# ABC2.net
KiCad netlist of a schematic drawn in Altium Designer
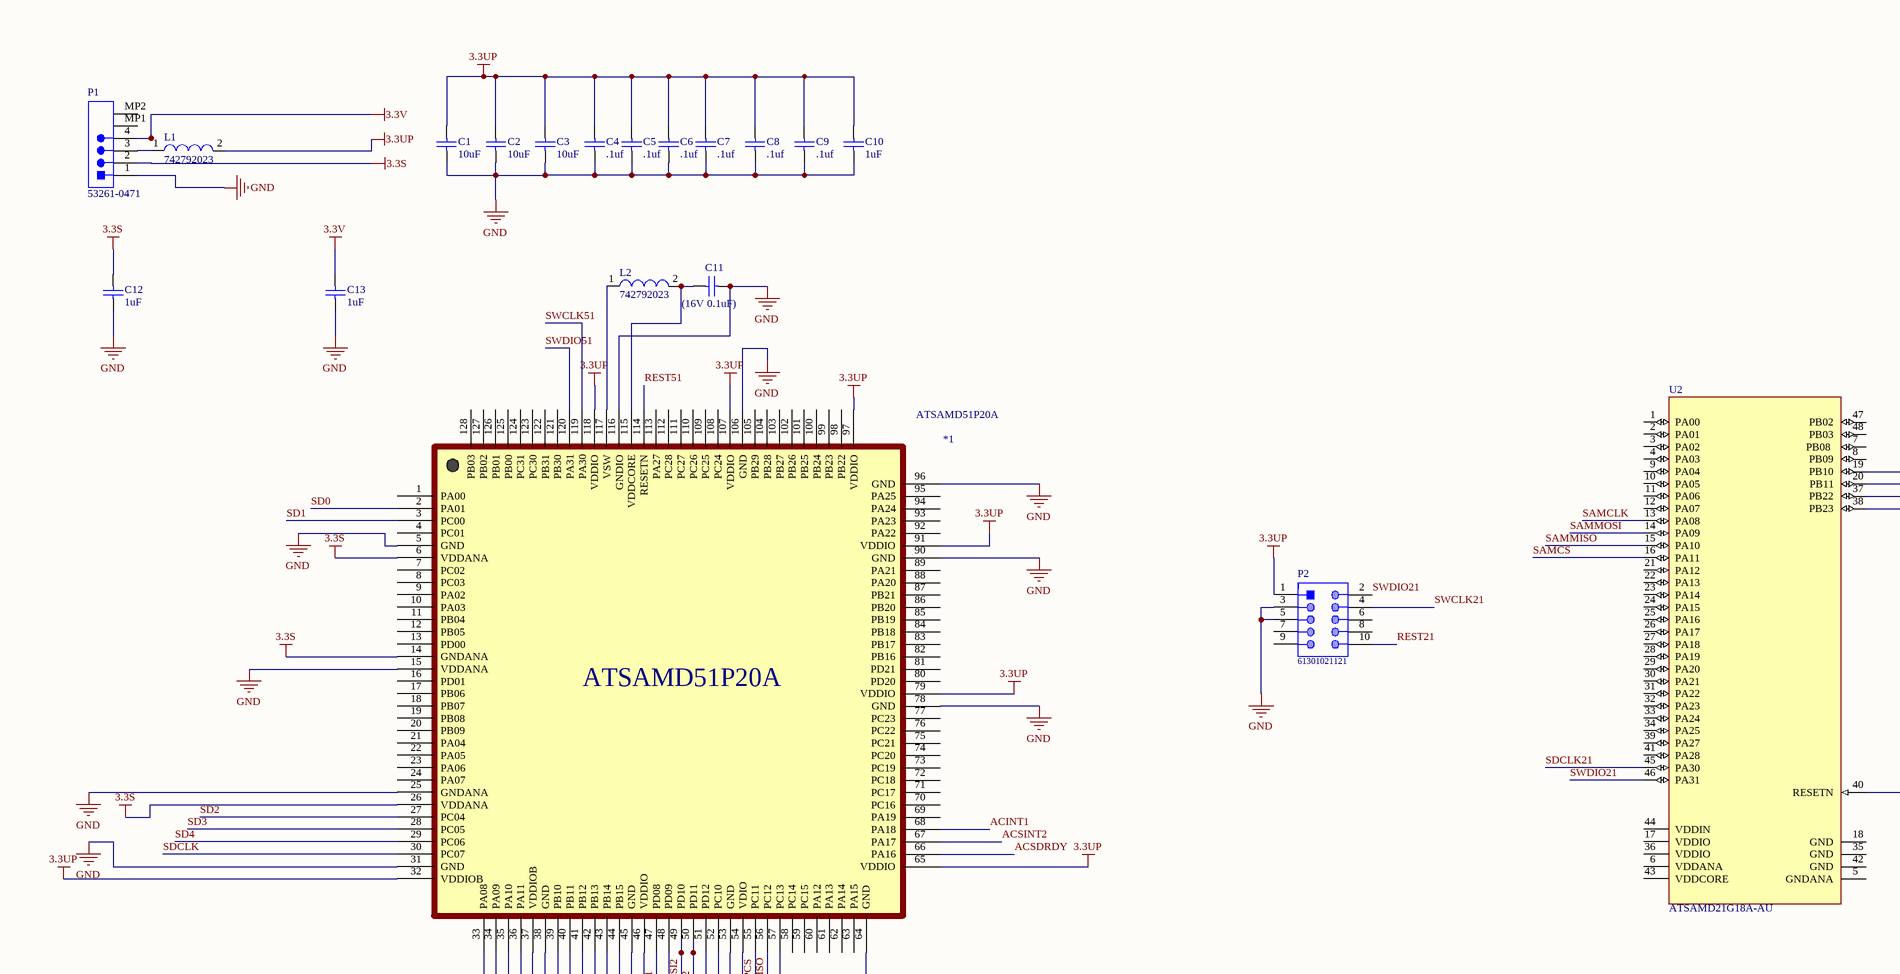
[diagram p0: ABC2.SchDoc, top left]
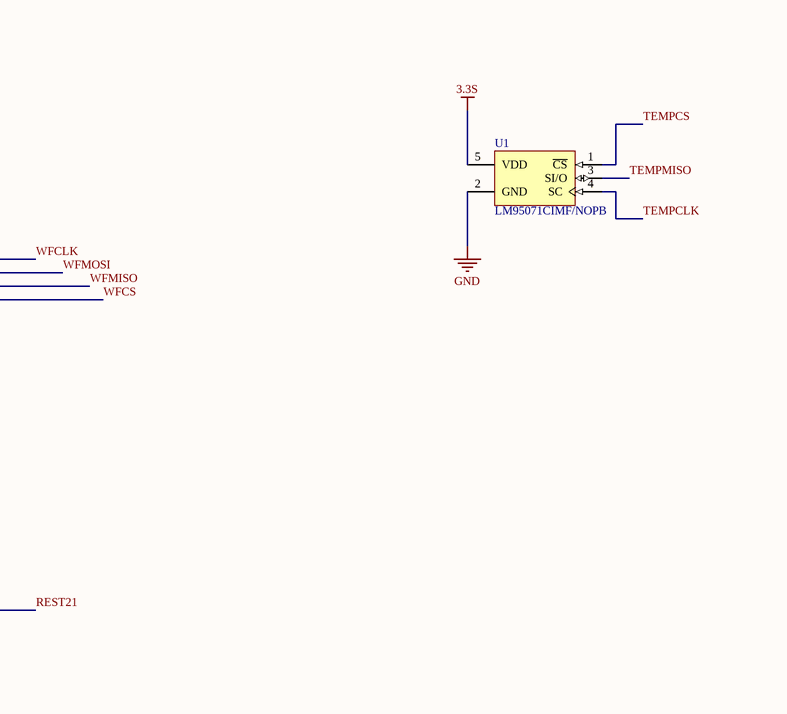
[diagram p1: ABC2.SchDoc, top right]
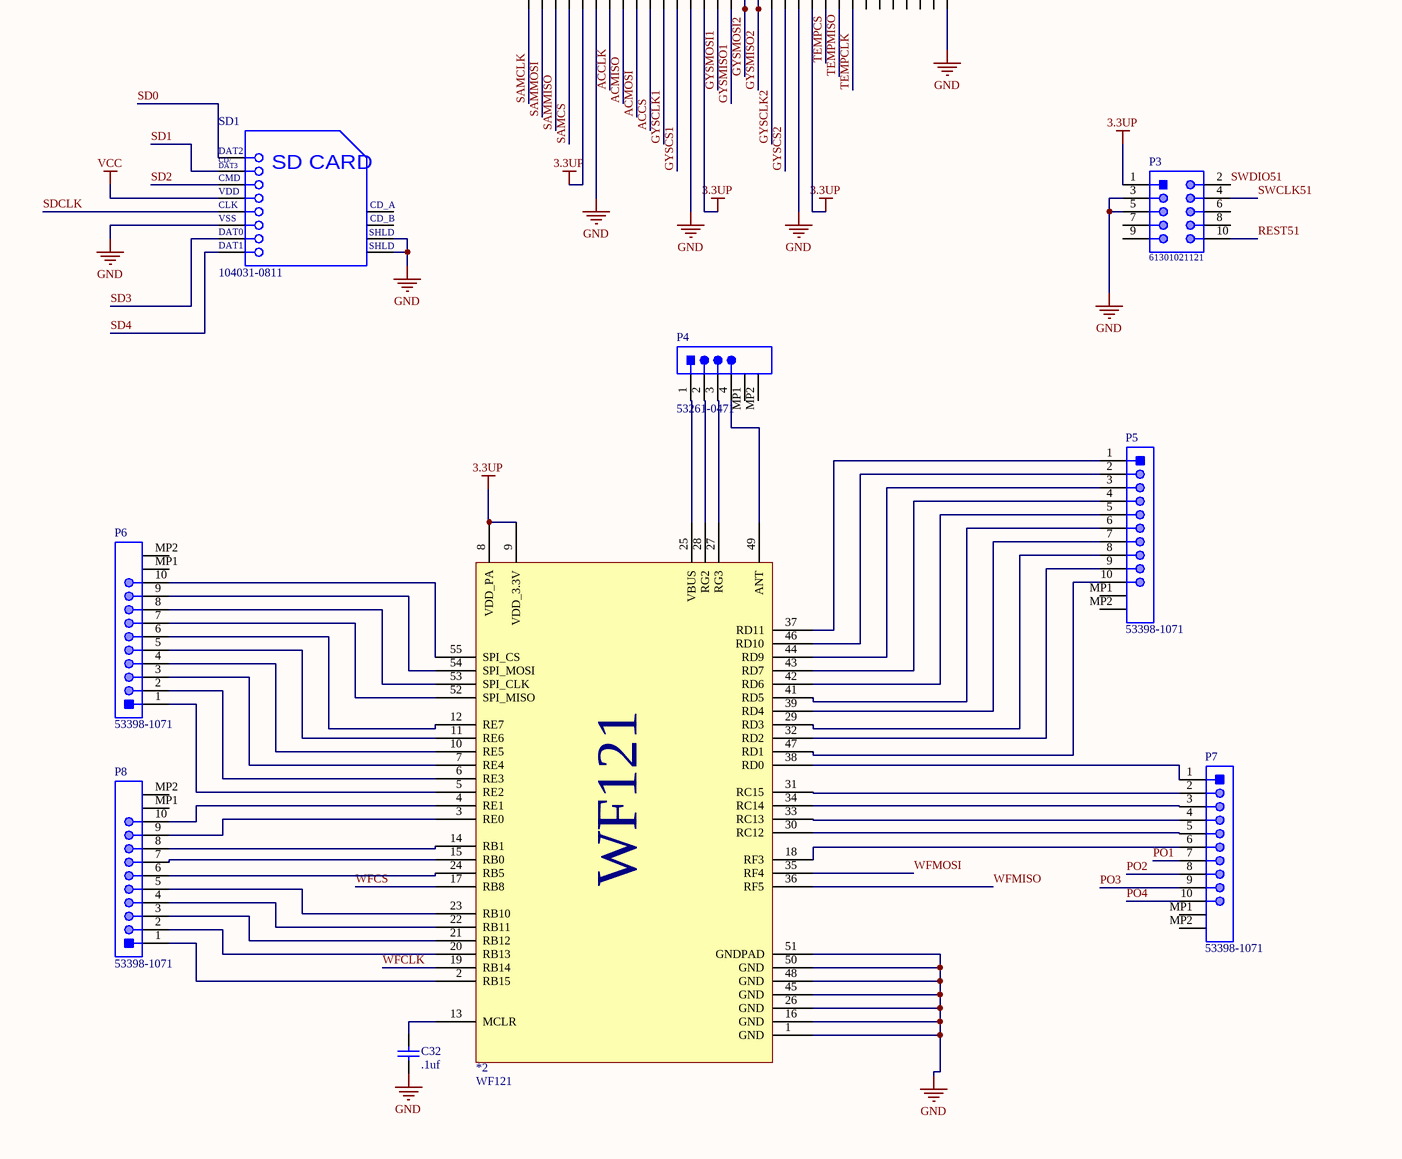
[diagram p2: ABC2.SchDoc, bottom left]
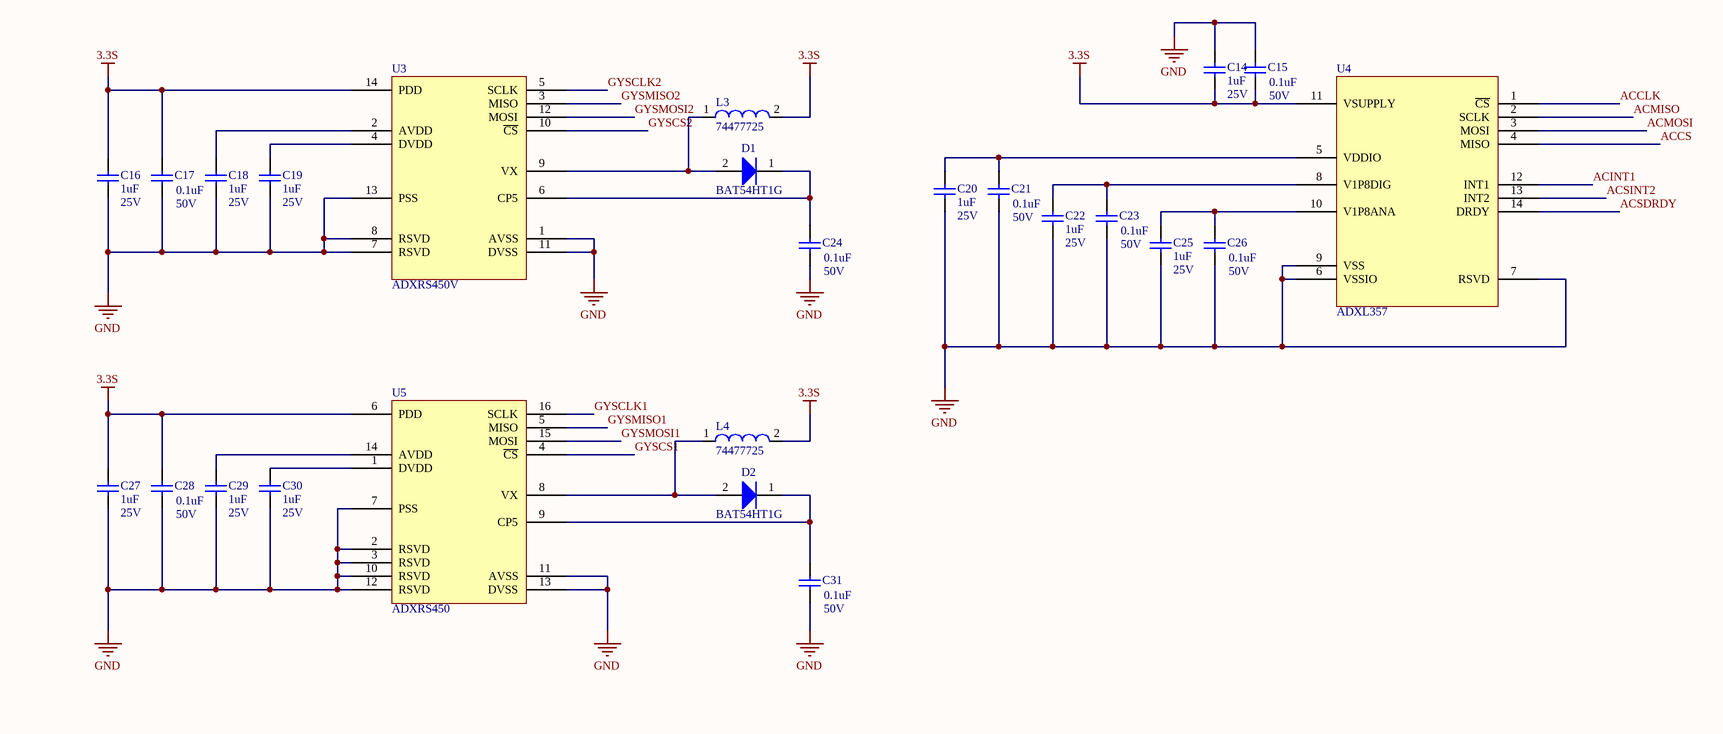
[diagram p3: ABC2.SchDoc, bottom right]

(export (version "E")
  (design (tool "Eeschema 10.0.6"))
  (components
    (comp (ref "*1")
      (value "ATSAMD51P20A")
      (footprint "ATSAMD51P20A")
      (description "https://www.microchip.com/wwwproducts/en/ATSAMD51P20A#additional-features")
      (libsource (lib "ATSAMD51P20A") (part "ATSAMD51P20A"))
    )
    (comp (ref "*2")
      (value "WF121")
      (footprint "WF121:WF121")
      (description "WF121 WIFI Module.")
      (libsource (lib "WF121") (part "WF121"))
    )
    (comp (ref "C1")
      (value "10uF")
      (footprint "CAPC1608X90X35NL10T15")
      (fields (field (name "PART NUMBER") "GRM188R60J106ME47D") (field (name "MANUFACTURER") "Murata"))
      (libsource (lib "Altium Content Vault") (part "CAP"))
    )
    (comp (ref "C2")
      (value "10uF")
      (footprint "CAPC1608X90X35NL10T15")
      (fields (field (name "PART NUMBER") "GRM188R60J106ME47D") (field (name "MANUFACTURER") "Murata"))
      (libsource (lib "Altium Content Vault") (part "CAP"))
    )
    (comp (ref "C3")
      (value "10uF")
      (footprint "CAPC1608X90X35NL10T15")
      (fields (field (name "PART NUMBER") "GRM188R60J106ME47D") (field (name "MANUFACTURER") "Murata"))
      (libsource (lib "Altium Content Vault") (part "CAP"))
    )
    (comp (ref "C4")
      (value ".1uf")
      (footprint "CAPC2013X94X50NL20T25")
      (fields
        (field (name "PART NUMBER") "0805YC104KAT2A")
        (field (name "MANUFACTURER") "AVX Interconnect / Elco")
      )
      (libsource (lib "Altium Content Vault") (part "CAP"))
    )
    (comp (ref "C5")
      (value ".1uf")
      (footprint "CAPC2013X94X50NL20T25")
      (fields
        (field (name "PART NUMBER") "0805YC104KAT2A")
        (field (name "MANUFACTURER") "AVX Interconnect / Elco")
      )
      (libsource (lib "Altium Content Vault") (part "CAP"))
    )
    (comp (ref "C6")
      (value ".1uf")
      (footprint "CAPC2013X94X50NL20T25")
      (fields
        (field (name "PART NUMBER") "0805YC104KAT2A")
        (field (name "MANUFACTURER") "AVX Interconnect / Elco")
      )
      (libsource (lib "Altium Content Vault") (part "CAP"))
    )
    (comp (ref "C7")
      (value ".1uf")
      (footprint "CAPC2013X94X50NL20T25")
      (fields
        (field (name "PART NUMBER") "0805YC104KAT2A")
        (field (name "MANUFACTURER") "AVX Interconnect / Elco")
      )
      (libsource (lib "Altium Content Vault") (part "CAP"))
    )
    (comp (ref "C8")
      (value ".1uf")
      (footprint "CAPC2013X94X50NL20T25")
      (fields
        (field (name "PART NUMBER") "0805YC104KAT2A")
        (field (name "MANUFACTURER") "AVX Interconnect / Elco")
      )
      (libsource (lib "Altium Content Vault") (part "CAP"))
    )
    (comp (ref "C9")
      (value ".1uf")
      (footprint "CAPC2013X94X50NL20T25")
      (fields
        (field (name "PART NUMBER") "0805YC104KAT2A")
        (field (name "MANUFACTURER") "AVX Interconnect / Elco")
      )
      (libsource (lib "Altium Content Vault") (part "CAP"))
    )
    (comp (ref "C10")
      (value "1uF")
      (footprint "CAPC1608X90X35LL15T15")
      (fields
        (field (name "PART NUMBER") "0603ZC105KAT2A")
        (field (name "MANUFACTURER") "AVX Interconnect / Elco")
      )
      (libsource (lib "Altium Content Vault") (part "CAP"))
    )
    (comp (ref "C11")
      (value "(16V 0.1uF)")
      (footprint "CAPC1608X90X35LL15T15")
      (fields
        (field (name "PART NUMBER") "0603YC104MAT4A")
        (field (name "MANUFACTURER") "AVX Interconnect / Elco")
      )
      (libsource (lib "Altium Content Vault") (part "CAP"))
    )
    (comp (ref "C12")
      (value "1uF")
      (footprint "CAPC1608X90X35LL15T15")
      (fields
        (field (name "PART NUMBER") "0603ZC105KAT2A")
        (field (name "MANUFACTURER") "AVX Interconnect / Elco")
      )
      (libsource (lib "Altium Content Vault") (part "CAP"))
    )
    (comp (ref "C13")
      (value "1uF")
      (footprint "CAPC1608X90X35LL15T15")
      (fields
        (field (name "PART NUMBER") "0603ZC105KAT2A")
        (field (name "MANUFACTURER") "AVX Interconnect / Elco")
      )
      (libsource (lib "Altium Content Vault") (part "CAP"))
    )
    (comp (ref "C14")
      (value "C0805C105K3RACTU")
      (footprint "CAPC2013X140X50LL20T25")
      (fields
        (field (name "MANUFACTURER") "Kemet")
        (field (name "CAPACITANCE") "1uF")
        (field (name "VOLTAGE RATING") "25V")
      )
      (libsource (lib "Altium Content Vault") (part "CAP"))
    )
    (comp (ref "C15")
      (value "CC0805KRX7R9BB104")
      (footprint "CAPC2013X95X50ML10T25")
      (description "Chip Capacitor, 100 nF, +/- 10%, 50 V, -55 to 125 degC, 0805 (2012 Metric), RoHS, Tape and Reel")
      (fields
        (field (name "VOLTAGE RATING") "50V")
        (field (name "TOLERANCE") "10%")
        (field (name "VOLTAGE") "50V")
        (field (name "CAPACITANCE") "0.1uF")
      )
      (libsource (lib "Altium Content Vault") (part "CAP-NP-2"))
    )
    (comp (ref "C16")
      (value "C0805C105K3RACTU")
      (footprint "CAPC2013X140X50LL20T25")
      (fields
        (field (name "MANUFACTURER") "Kemet")
        (field (name "CAPACITANCE") "1uF")
        (field (name "VOLTAGE RATING") "25V")
      )
      (libsource (lib "Altium Content Vault") (part "CAP"))
    )
    (comp (ref "C17")
      (value "CC0805KRX7R9BB104")
      (footprint "CAPC2013X95X50ML10T25")
      (description "Chip Capacitor, 100 nF, +/- 10%, 50 V, -55 to 125 degC, 0805 (2012 Metric), RoHS, Tape and Reel")
      (fields
        (field (name "VOLTAGE RATING") "50V")
        (field (name "TOLERANCE") "10%")
        (field (name "VOLTAGE") "50V")
        (field (name "CAPACITANCE") "0.1uF")
      )
      (libsource (lib "Altium Content Vault") (part "CAP-NP-2"))
    )
    (comp (ref "C18")
      (value "C0805C105K3RACTU")
      (footprint "CAPC2013X140X50LL20T25")
      (fields
        (field (name "MANUFACTURER") "Kemet")
        (field (name "CAPACITANCE") "1uF")
        (field (name "VOLTAGE RATING") "25V")
      )
      (libsource (lib "Altium Content Vault") (part "CAP"))
    )
    (comp (ref "C19")
      (value "C0805C105K3RACTU")
      (footprint "CAPC2013X140X50LL20T25")
      (fields
        (field (name "MANUFACTURER") "Kemet")
        (field (name "CAPACITANCE") "1uF")
        (field (name "VOLTAGE RATING") "25V")
      )
      (libsource (lib "Altium Content Vault") (part "CAP"))
    )
    (comp (ref "C20")
      (value "C0805C105K3RACTU")
      (footprint "CAPC2013X140X50LL20T25")
      (fields
        (field (name "MANUFACTURER") "Kemet")
        (field (name "CAPACITANCE") "1uF")
        (field (name "VOLTAGE RATING") "25V")
      )
      (libsource (lib "Altium Content Vault") (part "CAP"))
    )
    (comp (ref "C21")
      (value "CC0805KRX7R9BB104")
      (footprint "CAPC2013X95X50ML10T25")
      (description "Chip Capacitor, 100 nF, +/- 10%, 50 V, -55 to 125 degC, 0805 (2012 Metric), RoHS, Tape and Reel")
      (fields
        (field (name "VOLTAGE RATING") "50V")
        (field (name "TOLERANCE") "10%")
        (field (name "VOLTAGE") "50V")
        (field (name "CAPACITANCE") "0.1uF")
      )
      (libsource (lib "Altium Content Vault") (part "CAP-NP-2"))
    )
    (comp (ref "C22")
      (value "C0805C105K3RACTU")
      (footprint "CAPC2013X140X50LL20T25")
      (fields
        (field (name "MANUFACTURER") "Kemet")
        (field (name "CAPACITANCE") "1uF")
        (field (name "VOLTAGE RATING") "25V")
      )
      (libsource (lib "Altium Content Vault") (part "CAP"))
    )
    (comp (ref "C23")
      (value "CC0805KRX7R9BB104")
      (footprint "CAPC2013X95X50ML10T25")
      (description "Chip Capacitor, 100 nF, +/- 10%, 50 V, -55 to 125 degC, 0805 (2012 Metric), RoHS, Tape and Reel")
      (fields
        (field (name "VOLTAGE RATING") "50V")
        (field (name "TOLERANCE") "10%")
        (field (name "VOLTAGE") "50V")
        (field (name "CAPACITANCE") "0.1uF")
      )
      (libsource (lib "Altium Content Vault") (part "CAP-NP-2"))
    )
    (comp (ref "C24")
      (value "CC0805KRX7R9BB104")
      (footprint "CAPC2013X95X50ML10T25")
      (description "Chip Capacitor, 100 nF, +/- 10%, 50 V, -55 to 125 degC, 0805 (2012 Metric), RoHS, Tape and Reel")
      (fields
        (field (name "VOLTAGE RATING") "50V")
        (field (name "TOLERANCE") "10%")
        (field (name "VOLTAGE") "50V")
        (field (name "CAPACITANCE") "0.1uF")
      )
      (libsource (lib "Altium Content Vault") (part "CAP-NP-2"))
    )
    (comp (ref "C25")
      (value "C0805C105K3RACTU")
      (footprint "CAPC2013X140X50LL20T25")
      (fields
        (field (name "MANUFACTURER") "Kemet")
        (field (name "CAPACITANCE") "1uF")
        (field (name "VOLTAGE RATING") "25V")
      )
      (libsource (lib "Altium Content Vault") (part "CAP"))
    )
    (comp (ref "C26")
      (value "CC0805KRX7R9BB104")
      (footprint "CAPC2013X95X50ML10T25")
      (description "Chip Capacitor, 100 nF, +/- 10%, 50 V, -55 to 125 degC, 0805 (2012 Metric), RoHS, Tape and Reel")
      (fields
        (field (name "VOLTAGE RATING") "50V")
        (field (name "TOLERANCE") "10%")
        (field (name "VOLTAGE") "50V")
        (field (name "CAPACITANCE") "0.1uF")
      )
      (libsource (lib "Altium Content Vault") (part "CAP-NP-2"))
    )
    (comp (ref "C27")
      (value "C0805C105K3RACTU")
      (footprint "CAPC2013X140X50LL20T25")
      (fields
        (field (name "MANUFACTURER") "Kemet")
        (field (name "CAPACITANCE") "1uF")
        (field (name "VOLTAGE RATING") "25V")
      )
      (libsource (lib "Altium Content Vault") (part "CAP"))
    )
    (comp (ref "C28")
      (value "CC0805KRX7R9BB104")
      (footprint "CAPC2013X95X50ML10T25")
      (description "Chip Capacitor, 100 nF, +/- 10%, 50 V, -55 to 125 degC, 0805 (2012 Metric), RoHS, Tape and Reel")
      (fields
        (field (name "VOLTAGE RATING") "50V")
        (field (name "TOLERANCE") "10%")
        (field (name "VOLTAGE") "50V")
        (field (name "CAPACITANCE") "0.1uF")
      )
      (libsource (lib "Altium Content Vault") (part "CAP-NP-2"))
    )
    (comp (ref "C29")
      (value "C0805C105K3RACTU")
      (footprint "CAPC2013X140X50LL20T25")
      (fields
        (field (name "MANUFACTURER") "Kemet")
        (field (name "CAPACITANCE") "1uF")
        (field (name "VOLTAGE RATING") "25V")
      )
      (libsource (lib "Altium Content Vault") (part "CAP"))
    )
    (comp (ref "C30")
      (value "C0805C105K3RACTU")
      (footprint "CAPC2013X140X50LL20T25")
      (fields
        (field (name "MANUFACTURER") "Kemet")
        (field (name "CAPACITANCE") "1uF")
        (field (name "VOLTAGE RATING") "25V")
      )
      (libsource (lib "Altium Content Vault") (part "CAP"))
    )
    (comp (ref "C31")
      (value "CC0805KRX7R9BB104")
      (footprint "CAPC2013X95X50ML10T25")
      (description "Chip Capacitor, 100 nF, +/- 10%, 50 V, -55 to 125 degC, 0805 (2012 Metric), RoHS, Tape and Reel")
      (fields
        (field (name "VOLTAGE RATING") "50V")
        (field (name "TOLERANCE") "10%")
        (field (name "VOLTAGE") "50V")
        (field (name "CAPACITANCE") "0.1uF")
      )
      (libsource (lib "Altium Content Vault") (part "CAP-NP-2"))
    )
    (comp (ref "C32")
      (value ".1uf")
      (footprint "CAPC2013X94X50NL20T25")
      (fields
        (field (name "PART NUMBER") "0805YC104KAT2A")
        (field (name "MANUFACTURER") "AVX Interconnect / Elco")
      )
      (libsource (lib "Altium Content Vault") (part "CAP"))
    )
    (comp (ref "D1")
      (value "BAT54HT1G")
      (footprint "ONSC-SOD-323-2-477-02_V")
      (description "Schottky Barrier Diode, 2-Pin SOD-323, Pb-Free, Tape and Reel")
      (fields (field (name "MANUFACTURER") "On Semiconductor"))
      (libsource (lib "Altium Content Vault") (part "ONSC-D-K1A2-2"))
    )
    (comp (ref "D2")
      (value "BAT54HT1G")
      (footprint "ONSC-SOD-323-2-477-02_V")
      (description "Schottky Barrier Diode, 2-Pin SOD-323, Pb-Free, Tape and Reel")
      (fields (field (name "MANUFACTURER") "On Semiconductor"))
      (libsource (lib "Altium Content Vault") (part "ONSC-D-K1A2-2"))
    )
    (comp (ref "L1")
      (value "742792023")
      (footprint "SMD-0805")
      (description "SMD EMI Suppression Ferrite Bead WE-CBF, Z = 120 Ohm")
      (libsource (lib "Altium Content Vault") (part "PAS-IND-INDUCTOR-2"))
    )
    (comp (ref "L2")
      (value "742792023")
      (footprint "SMD-0805")
      (description "SMD EMI Suppression Ferrite Bead WE-CBF, Z = 120 Ohm")
      (libsource (lib "Altium Content Vault") (part "PAS-IND-INDUCTOR-2"))
    )
    (comp (ref "L3")
      (value "74477725")
      (footprint "WE-PD-M")
      (description "SMD-Shielded Power Inductor WE-PD, L = 560 µH")
      (libsource (lib "Altium Content Vault") (part "PAS-IND-INDUCTOR-2"))
    )
    (comp (ref "L4")
      (value "74477725")
      (footprint "WE-PD-M")
      (description "SMD-Shielded Power Inductor WE-PD, L = 560 µH")
      (libsource (lib "Altium Content Vault") (part "PAS-IND-INDUCTOR-2"))
    )
    (comp (ref "P1")
      (value "53261-0471")
      (footprint "MOLEX-53261-0471_V")
      (description "Male Header, Pitch 1.25 mm, 1 x 4 Position, Height 3.4 mm, -40 to 85 degC, RoHS, Tape and Reel")
      (fields (field (name "MANUFACTURER") "Molex"))
      (libsource (lib "") (part "CN-1P-2M-R4_A_1"))
    )
    (comp (ref "P2")
      (value "61301021121")
      (footprint "61301021121")
      (description "THT Vertical Pin Header WR-PHD, Pitch 2.54 mm, Dual Row, 10 pins")
      (fields (field (name "MANUFACTURER") "Wurth Elektronik") (field (name "PUBLISHER") "WurthElektronik"))
      (libsource (lib "Altium Content Vault") (part "WE-CN-2P-M-R10"))
    )
    (comp (ref "P3")
      (value "61301021121")
      (footprint "61301021121")
      (description "THT Vertical Pin Header WR-PHD, Pitch 2.54 mm, Dual Row, 10 pins")
      (fields (field (name "MANUFACTURER") "Wurth Elektronik") (field (name "PUBLISHER") "WurthElektronik"))
      (libsource (lib "Altium Content Vault") (part "WE-CN-2P-M-R10"))
    )
    (comp (ref "P4")
      (value "53261-0471")
      (footprint "MOLEX-53261-0471_V")
      (description "Male Header, Pitch 1.25 mm, 1 x 4 Position, Height 3.4 mm, -40 to 85 degC, RoHS, Tape and Reel")
      (fields (field (name "MANUFACTURER") "Molex"))
      (libsource (lib "Altium Content Vault") (part "CN-1P-2M-R4_A"))
    )
    (comp (ref "P5")
      (value "53398-1071")
      (footprint "MOLX-53398-1071_V")
      (description "Male Header, Pitch 1.25 mm, 1 x 10 Position, Height 4.7 mm, -40 to 85 degC, RoHS, Tape and Reel")
      (fields (field (name "MANUFACTURER") "Molex"))
      (libsource (lib "") (part "CN-1P-2M-R10_1"))
    )
    (comp (ref "P6")
      (value "53398-1071")
      (footprint "MOLX-53398-1071_V")
      (description "Male Header, Pitch 1.25 mm, 1 x 10 Position, Height 4.7 mm, -40 to 85 degC, RoHS, Tape and Reel")
      (fields (field (name "MANUFACTURER") "Molex"))
      (libsource (lib "Altium Content Vault") (part "CN-1P-2M-R10"))
    )
    (comp (ref "P7")
      (value "53398-1071")
      (footprint "MOLX-53398-1071_V")
      (description "Male Header, Pitch 1.25 mm, 1 x 10 Position, Height 4.7 mm, -40 to 85 degC, RoHS, Tape and Reel")
      (fields (field (name "MANUFACTURER") "Molex"))
      (libsource (lib "") (part "CN-1P-2M-R10_1"))
    )
    (comp (ref "P8")
      (value "53398-1071")
      (footprint "MOLX-53398-1071_V")
      (description "Male Header, Pitch 1.25 mm, 1 x 10 Position, Height 4.7 mm, -40 to 85 degC, RoHS, Tape and Reel")
      (fields (field (name "MANUFACTURER") "Molex"))
      (libsource (lib "Altium Content Vault") (part "CN-1P-2M-R10"))
    )
    (comp (ref "SD1")
      (value "104031-0811")
      (footprint "MOLX-104031-0811_V")
      (description "Micro SD Card, RA, -25 to 85 degC, 8-Pin SMD, RoHS, Tape and Reel")
      (fields (field (name "MANUFACTURER") "Molex"))
      (libsource (lib "Altium Content Vault") (part "CN-SD-8-2SW-2S"))
    )
    (comp (ref "U1")
      (value "LM95071CIMF/NOPB")
      (footprint "DBV0005A_L")
      (description "SPI/MICROWIRE 13-Bit Plus Sign Temperature Sensor, 5-pin SOT-23, Pb-Free")
      (fields (field (name "MANUFACTURER") "Texas Instruments"))
      (libsource (lib "Altium Content Vault") (part "SEN-TEMP-LM95071CIMF-5"))
    )
    (comp (ref "U2")
      (value "ATSAMD21G18A-AU")
      (footprint "ATML-TQFP48_M")
      (fields (field (name "MANUFACTURER") "Atmel"))
      (libsource (lib "SAMD21") (part "CMP-2100-03585-1"))
    )
    (comp (ref "U3")
      (value "ADXRS450V")
      (footprint "LCC127P900X400X915-14N")
      (libsource (lib "CFClib") (part "ADXRS450V"))
    )
    (comp (ref "U4")
      (value "ADXL357")
      (footprint "LCCS127P605X560X220-14N")
      (libsource (lib "CFClib") (part "ADXL357"))
    )
    (comp (ref "U5")
      (value "ADXRS450")
      (footprint "SOIC127P1040X373-16N")
      (libsource (lib "CFClib") (part "ADXRS450"))
    )
  )
  (nets
    (net (code "1") (name "/ACCLK") (class "Default")
      (node (ref "*1") (pin "39") (pinfunction "PB10_39") (pintype "passive"))
      (node (ref "U4") (pin "1") (pinfunction "~{CS}_1") (pintype "passive"))
    )
    (net (code "2") (name "/ACCS") (class "Default")
      (node (ref "*1") (pin "42") (pinfunction "PB13_42") (pintype "passive"))
      (node (ref "U4") (pin "4") (pinfunction "MISO_4") (pintype "passive"))
    )
    (net (code "3") (name "/ACINT1") (class "Default")
      (node (ref "*1") (pin "68") (pinfunction "PA18_68") (pintype "passive"))
      (node (ref "U4") (pin "12") (pinfunction "INT1_12") (pintype "passive"))
    )
    (net (code "4") (name "/ACMISO") (class "Default")
      (node (ref "*1") (pin "40") (pinfunction "PB11_40") (pintype "passive"))
      (node (ref "U4") (pin "2") (pinfunction "SCLK_2") (pintype "passive"))
    )
    (net (code "5") (name "/ACMOSI") (class "Default")
      (node (ref "*1") (pin "41") (pinfunction "PB12_41") (pintype "passive"))
      (node (ref "U4") (pin "3") (pinfunction "MOSI_3") (pintype "passive"))
    )
    (net (code "6") (name "/ACSDRDY") (class "Default")
      (node (ref "*1") (pin "66") (pinfunction "PA16_66") (pintype "passive"))
      (node (ref "U4") (pin "14") (pinfunction "DRDY_14") (pintype "passive"))
    )
    (net (code "7") (name "/ACSINT2") (class "Default")
      (node (ref "*1") (pin "67") (pinfunction "PA17_67") (pintype "passive"))
      (node (ref "U4") (pin "13") (pinfunction "INT2_13") (pintype "passive"))
    )
    (net (code "8") (name "/GYSCLK1") (class "Default")
      (node (ref "*1") (pin "43") (pinfunction "PB14_43") (pintype "passive"))
      (node (ref "U5") (pin "16") (pinfunction "SCLK_16") (pintype "passive"))
    )
    (net (code "9") (name "/GYSCLK2") (class "Default")
      (node (ref "*1") (pin "51") (pinfunction "PD12_51") (pintype "passive"))
      (node (ref "U3") (pin "5") (pinfunction "SCLK_5") (pintype "passive"))
    )
    (net (code "10") (name "/GYSCS1") (class "Default")
      (node (ref "*1") (pin "44") (pinfunction "PB15_44") (pintype "passive"))
      (node (ref "U5") (pin "4") (pinfunction "~{CS}_4") (pintype "passive"))
    )
    (net (code "11") (name "/GYSCS2") (class "Default")
      (node (ref "*1") (pin "52") (pinfunction "PC10_52") (pintype "passive"))
      (node (ref "U3") (pin "10") (pinfunction "~{CS}_10") (pintype "passive"))
    )
    (net (code "12") (name "/GYSMISO1") (class "Default")
      (node (ref "*1") (pin "48") (pinfunction "PD09_48") (pintype "passive"))
      (node (ref "U5") (pin "5") (pinfunction "MISO_5") (pintype "passive"))
    )
    (net (code "13") (name "/GYSMISO2") (class "Default")
      (node (ref "*1") (pin "50") (pinfunction "PD11_50") (pintype "passive"))
      (node (ref "U3") (pin "3") (pinfunction "MISO_3") (pintype "passive"))
    )
    (net (code "14") (name "/GYSMOSI1") (class "Default")
      (node (ref "*1") (pin "47") (pinfunction "PD08_47") (pintype "passive"))
      (node (ref "U5") (pin "15") (pinfunction "MOSI_15") (pintype "passive"))
    )
    (net (code "15") (name "/GYSMOSI2") (class "Default")
      (node (ref "*1") (pin "49") (pinfunction "PD10_49") (pintype "passive"))
      (node (ref "U3") (pin "12") (pinfunction "MOSI_12") (pintype "passive"))
    )
    (net (code "16") (name "/PO1") (class "Default")
      (node (ref "P7") (pin "7") (pinfunction "7_7") (pintype "passive"))
    )
    (net (code "17") (name "/PO2") (class "Default")
      (node (ref "P7") (pin "8") (pinfunction "8_8") (pintype "passive"))
    )
    (net (code "18") (name "/PO3") (class "Default")
      (node (ref "P7") (pin "9") (pinfunction "9_9") (pintype "passive"))
    )
    (net (code "19") (name "/PO4") (class "Default")
      (node (ref "P7") (pin "10") (pinfunction "10_10") (pintype "passive"))
    )
    (net (code "20") (name "/REST21") (class "Default")
      (node (ref "P2") (pin "10") (pinfunction "10_10") (pintype "passive"))
      (node (ref "U2") (pin "40") (pinfunction "RESETN_40") (pintype "input"))
    )
    (net (code "21") (name "/REST51") (class "Default")
      (node (ref "*1") (pin "114") (pinfunction "RESETN_114") (pintype "passive"))
      (node (ref "P3") (pin "10") (pinfunction "10_10") (pintype "passive"))
    )
    (net (code "22") (name "/SAMCLK") (class "Default")
      (node (ref "*1") (pin "33") (pinfunction "PA08_33") (pintype "passive"))
      (node (ref "U2") (pin "13") (pinfunction "PA08_13") (pintype "bidirectional"))
    )
    (net (code "23") (name "/SAMCS") (class "Default")
      (node (ref "*1") (pin "36") (pinfunction "PA11_36") (pintype "passive"))
      (node (ref "U2") (pin "16") (pinfunction "PA11_16") (pintype "bidirectional"))
    )
    (net (code "24") (name "/SAMMISO") (class "Default")
      (node (ref "*1") (pin "35") (pinfunction "PA10_35") (pintype "passive"))
      (node (ref "U2") (pin "15") (pinfunction "PA10_15") (pintype "bidirectional"))
    )
    (net (code "25") (name "/SAMMOSI") (class "Default")
      (node (ref "*1") (pin "34") (pinfunction "PA09_34") (pintype "passive"))
      (node (ref "U2") (pin "14") (pinfunction "PA09_14") (pintype "bidirectional"))
    )
    (net (code "26") (name "/SD0") (class "Default")
      (node (ref "*1") (pin "2") (pinfunction "PA01_2") (pintype "passive"))
      (node (ref "SD1") (pin "1") (pinfunction "CD/DAT3_1") (pintype "passive"))
    )
    (net (code "27") (name "/SD1") (class "Default")
      (node (ref "*1") (pin "3") (pinfunction "PC00_3") (pintype "passive"))
      (node (ref "SD1") (pin "2") (pinfunction "CMD_2") (pintype "passive"))
    )
    (net (code "28") (name "/SD2") (class "Default")
      (node (ref "*1") (pin "27") (pinfunction "PC04_27") (pintype "passive"))
      (node (ref "SD1") (pin "3") (pinfunction "VSS1_3") (pintype "passive"))
    )
    (net (code "29") (name "/SD3") (class "Default")
      (node (ref "*1") (pin "28") (pinfunction "PC05_28") (pintype "passive"))
      (node (ref "SD1") (pin "7") (pinfunction "DAT0_7") (pintype "passive"))
    )
    (net (code "30") (name "/SD4") (class "Default")
      (node (ref "*1") (pin "29") (pinfunction "PC06_29") (pintype "passive"))
      (node (ref "SD1") (pin "8") (pinfunction "DAT1_8") (pintype "passive"))
    )
    (net (code "31") (name "/SDCLK") (class "Default")
      (node (ref "*1") (pin "30") (pinfunction "PC07_30") (pintype "passive"))
      (node (ref "SD1") (pin "5") (pinfunction "CLK_5") (pintype "passive"))
    )
    (net (code "32") (name "/SDCLK21") (class "Default")
      (node (ref "U2") (pin "45") (pinfunction "PA30_45") (pintype "bidirectional"))
    )
    (net (code "33") (name "/SWCLK21") (class "Default")
      (node (ref "P2") (pin "4") (pinfunction "4_4") (pintype "passive"))
    )
    (net (code "34") (name "/SWCLK51") (class "Default")
      (node (ref "*1") (pin "119") (pinfunction "PA30_119") (pintype "passive"))
      (node (ref "P3") (pin "4") (pinfunction "4_4") (pintype "passive"))
    )
    (net (code "35") (name "/SWDIO21") (class "Default")
      (node (ref "P2") (pin "2") (pinfunction "2_2") (pintype "passive"))
      (node (ref "U2") (pin "46") (pinfunction "PA31_46") (pintype "bidirectional"))
    )
    (net (code "36") (name "/SWDIO51") (class "Default")
      (node (ref "*1") (pin "120") (pinfunction "PA31_120") (pintype "passive"))
      (node (ref "P3") (pin "2") (pinfunction "2_2") (pintype "passive"))
    )
    (net (code "37") (name "/TEMPCLK") (class "Default")
      (node (ref "*1") (pin "57") (pinfunction "PC13_57") (pintype "passive"))
      (node (ref "U1") (pin "4") (pinfunction "SC_4") (pintype "input"))
    )
    (net (code "38") (name "/TEMPCS") (class "Default")
      (node (ref "*1") (pin "55") (pinfunction "PC11_55") (pintype "passive"))
      (node (ref "U1") (pin "1") (pinfunction "~{CS}_1") (pintype "input"))
    )
    (net (code "39") (name "/TEMPMISO") (class "Default")
      (node (ref "*1") (pin "56") (pinfunction "PC12_56") (pintype "passive"))
      (node (ref "U1") (pin "3") (pinfunction "SI/O_3") (pintype "bidirectional"))
    )
    (net (code "40") (name "/WFCLK") (class "Default")
      (node (ref "*2") (pin "19") (pinfunction "RB14_19") (pintype "passive"))
      (node (ref "U2") (pin "19") (pinfunction "PB10_19") (pintype "bidirectional"))
    )
    (net (code "41") (name "/WFCS") (class "Default")
      (node (ref "*2") (pin "17") (pinfunction "RB8_17") (pintype "passive"))
      (node (ref "U2") (pin "38") (pinfunction "PB23_38") (pintype "bidirectional"))
    )
    (net (code "42") (name "/WFMISO") (class "Default")
      (node (ref "*2") (pin "36") (pinfunction "RF5_36") (pintype "passive"))
      (node (ref "U2") (pin "37") (pinfunction "PB22_37") (pintype "bidirectional"))
    )
    (net (code "43") (name "/WFMOSI") (class "Default")
      (node (ref "*2") (pin "35") (pinfunction "RF4_35") (pintype "passive"))
      (node (ref "U2") (pin "20") (pinfunction "PB11_20") (pintype "bidirectional"))
    )
    (net (code "44") (name "3.3S") (class "Default")
      (node (ref "*1") (pin "14") (pinfunction "GNDANA_14") (pintype "passive"))
      (node (ref "*1") (pin "26") (pinfunction "VDDANA_26") (pintype "passive"))
      (node (ref "*1") (pin "6") (pinfunction "VDDANA_6") (pintype "passive"))
      (node (ref "C12") (pin "1") (pinfunction "1_1") (pintype "passive"))
      (node (ref "C14") (pin "2") (pinfunction "2_2") (pintype "passive"))
      (node (ref "C15") (pin "2") (pinfunction "2_2") (pintype "passive"))
      (node (ref "C16") (pin "1") (pinfunction "1_1") (pintype "passive"))
      (node (ref "C17") (pin "1") (pinfunction "1_1") (pintype "passive"))
      (node (ref "C27") (pin "1") (pinfunction "1_1") (pintype "passive"))
      (node (ref "C28") (pin "1") (pinfunction "1_1") (pintype "passive"))
      (node (ref "L3") (pin "2") (pinfunction "2_2") (pintype "passive"))
      (node (ref "L4") (pin "2") (pinfunction "2_2") (pintype "passive"))
      (node (ref "P1") (pin "2") (pinfunction "2_2") (pintype "passive"))
      (node (ref "U1") (pin "5") (pinfunction "VDD_5") (pintype "power_in"))
      (node (ref "U3") (pin "14") (pinfunction "PDD_14") (pintype "passive"))
      (node (ref "U4") (pin "11") (pinfunction "VSUPPLY_11") (pintype "passive"))
      (node (ref "U5") (pin "6") (pinfunction "PDD_6") (pintype "passive"))
    )
    (net (code "45") (name "3.3UP") (class "Default")
      (node (ref "*1") (pin "107") (pinfunction "VDDIO_107") (pintype "passive"))
      (node (ref "*1") (pin "118") (pinfunction "VDDIO_118") (pintype "passive"))
      (node (ref "*1") (pin "32") (pinfunction "VDDIOB_32") (pintype "passive"))
      (node (ref "*1") (pin "37") (pinfunction "VDDIOB_37") (pintype "passive"))
      (node (ref "*1") (pin "46") (pinfunction "VDDIO_46") (pintype "passive"))
      (node (ref "*1") (pin "54") (pinfunction "VDIO_54") (pintype "passive"))
      (node (ref "*1") (pin "65") (pinfunction "VDDIO_65") (pintype "passive"))
      (node (ref "*1") (pin "79") (pinfunction "VDDIO_79") (pintype "passive"))
      (node (ref "*1") (pin "91") (pinfunction "VDDIO_91") (pintype "passive"))
      (node (ref "*1") (pin "97") (pinfunction "VDDIO_97") (pintype "passive"))
      (node (ref "*2") (pin "8") (pinfunction "VDD_PA_8") (pintype "passive"))
      (node (ref "*2") (pin "9") (pinfunction "VDD_3.3V_9") (pintype "passive"))
      (node (ref "C1") (pin "2") (pinfunction "2_2") (pintype "passive"))
      (node (ref "C10") (pin "2") (pinfunction "2_2") (pintype "passive"))
      (node (ref "C2") (pin "2") (pinfunction "2_2") (pintype "passive"))
      (node (ref "C3") (pin "2") (pinfunction "2_2") (pintype "passive"))
      (node (ref "C4") (pin "2") (pinfunction "2_2") (pintype "passive"))
      (node (ref "C5") (pin "2") (pinfunction "2_2") (pintype "passive"))
      (node (ref "C6") (pin "2") (pinfunction "2_2") (pintype "passive"))
      (node (ref "C7") (pin "2") (pinfunction "2_2") (pintype "passive"))
      (node (ref "C8") (pin "2") (pinfunction "2_2") (pintype "passive"))
      (node (ref "C9") (pin "2") (pinfunction "2_2") (pintype "passive"))
      (node (ref "L1") (pin "2") (pinfunction "2_2") (pintype "passive"))
      (node (ref "P2") (pin "1") (pinfunction "1_1") (pintype "passive"))
      (node (ref "P3") (pin "1") (pinfunction "1_1") (pintype "passive"))
    )
    (net (code "46") (name "3.3V") (class "Default")
      (node (ref "C13") (pin "1") (pinfunction "1_1") (pintype "passive"))
      (node (ref "P1") (pin "4") (pinfunction "4_4") (pintype "passive"))
    )
    (net (code "47") (name "GND") (class "Default")
      (node (ref "*1") (pin "106") (pinfunction "GND_106") (pintype "passive"))
      (node (ref "*1") (pin "116") (pinfunction "GNDIO_116") (pintype "passive"))
      (node (ref "*1") (pin "15") (pinfunction "VDDANA_15") (pintype "passive"))
      (node (ref "*1") (pin "25") (pinfunction "GNDANA_25") (pintype "passive"))
      (node (ref "*1") (pin "31") (pinfunction "GND_31") (pintype "passive"))
      (node (ref "*1") (pin "38") (pinfunction "GND_38") (pintype "passive"))
      (node (ref "*1") (pin "45") (pinfunction "GND_45") (pintype "passive"))
      (node (ref "*1") (pin "5") (pinfunction "GND_5") (pintype "passive"))
      (node (ref "*1") (pin "53") (pinfunction "GND_53") (pintype "passive"))
      (node (ref "*1") (pin "64") (pinfunction "GND_64") (pintype "passive"))
      (node (ref "*1") (pin "78") (pinfunction "GND_78") (pintype "passive"))
      (node (ref "*1") (pin "90") (pinfunction "GND_90") (pintype "passive"))
      (node (ref "*1") (pin "96") (pinfunction "GND_96") (pintype "passive"))
      (node (ref "*2") (pin "1") (pinfunction "GND_1") (pintype "passive"))
      (node (ref "*2") (pin "16") (pinfunction "GND_16") (pintype "passive"))
      (node (ref "*2") (pin "26") (pinfunction "GND_26") (pintype "passive"))
      (node (ref "*2") (pin "45") (pinfunction "GND_45") (pintype "passive"))
      (node (ref "*2") (pin "48") (pinfunction "GND_48") (pintype "passive"))
      (node (ref "*2") (pin "50") (pinfunction "GND_50") (pintype "passive"))
      (node (ref "*2") (pin "51") (pinfunction "GNDPAD_51") (pintype "passive"))
      (node (ref "C1") (pin "1") (pinfunction "1_1") (pintype "passive"))
      (node (ref "C10") (pin "1") (pinfunction "1_1") (pintype "passive"))
      (node (ref "C11") (pin "2") (pinfunction "2_2") (pintype "passive"))
      (node (ref "C12") (pin "2") (pinfunction "2_2") (pintype "passive"))
      (node (ref "C13") (pin "2") (pinfunction "2_2") (pintype "passive"))
      (node (ref "C14") (pin "1") (pinfunction "1_1") (pintype "passive"))
      (node (ref "C15") (pin "1") (pinfunction "1_1") (pintype "passive"))
      (node (ref "C16") (pin "2") (pinfunction "2_2") (pintype "passive"))
      (node (ref "C17") (pin "2") (pinfunction "2_2") (pintype "passive"))
      (node (ref "C18") (pin "2") (pinfunction "2_2") (pintype "passive"))
      (node (ref "C19") (pin "2") (pinfunction "2_2") (pintype "passive"))
      (node (ref "C2") (pin "1") (pinfunction "1_1") (pintype "passive"))
      (node (ref "C20") (pin "2") (pinfunction "2_2") (pintype "passive"))
      (node (ref "C21") (pin "2") (pinfunction "2_2") (pintype "passive"))
      (node (ref "C22") (pin "2") (pinfunction "2_2") (pintype "passive"))
      (node (ref "C23") (pin "2") (pinfunction "2_2") (pintype "passive"))
      (node (ref "C24") (pin "2") (pinfunction "2_2") (pintype "passive"))
      (node (ref "C25") (pin "2") (pinfunction "2_2") (pintype "passive"))
      (node (ref "C26") (pin "2") (pinfunction "2_2") (pintype "passive"))
      (node (ref "C27") (pin "2") (pinfunction "2_2") (pintype "passive"))
      (node (ref "C28") (pin "2") (pinfunction "2_2") (pintype "passive"))
      (node (ref "C29") (pin "2") (pinfunction "2_2") (pintype "passive"))
      (node (ref "C3") (pin "1") (pinfunction "1_1") (pintype "passive"))
      (node (ref "C30") (pin "2") (pinfunction "2_2") (pintype "passive"))
      (node (ref "C31") (pin "2") (pinfunction "2_2") (pintype "passive"))
      (node (ref "C32") (pin "1") (pinfunction "1_1") (pintype "passive"))
      (node (ref "C4") (pin "1") (pinfunction "1_1") (pintype "passive"))
      (node (ref "C5") (pin "1") (pinfunction "1_1") (pintype "passive"))
      (node (ref "C6") (pin "1") (pinfunction "1_1") (pintype "passive"))
      (node (ref "C7") (pin "1") (pinfunction "1_1") (pintype "passive"))
      (node (ref "C8") (pin "1") (pinfunction "1_1") (pintype "passive"))
      (node (ref "C9") (pin "1") (pinfunction "1_1") (pintype "passive"))
      (node (ref "P1") (pin "1") (pinfunction "1_1") (pintype "passive"))
      (node (ref "P2") (pin "3") (pinfunction "3_3") (pintype "passive"))
      (node (ref "P2") (pin "5") (pinfunction "5_5") (pintype "passive"))
      (node (ref "P3") (pin "3") (pinfunction "3_3") (pintype "passive"))
      (node (ref "P3") (pin "5") (pinfunction "5_5") (pintype "passive"))
      (node (ref "SD1") (pin "11") (pinfunction "SHLD1_11") (pintype "passive"))
      (node (ref "SD1") (pin "12") (pinfunction "SHLD2_12") (pintype "passive"))
      (node (ref "SD1") (pin "6") (pinfunction "VSS2_6") (pintype "passive"))
      (node (ref "U1") (pin "2") (pinfunction "GND_2") (pintype "power_in"))
      (node (ref "U3") (pin "1") (pinfunction "AVSS_1") (pintype "passive"))
      (node (ref "U3") (pin "11") (pinfunction "DVSS_11") (pintype "passive"))
      (node (ref "U3") (pin "13") (pinfunction "PSS_13") (pintype "passive"))
      (node (ref "U3") (pin "7") (pinfunction "RSVD_7") (pintype "passive"))
      (node (ref "U3") (pin "8") (pinfunction "RSVD_8") (pintype "passive"))
      (node (ref "U4") (pin "6") (pinfunction "VSSIO_6") (pintype "passive"))
      (node (ref "U4") (pin "7") (pinfunction "RSVD_7") (pintype "passive"))
      (node (ref "U4") (pin "9") (pinfunction "VSS_9") (pintype "passive"))
      (node (ref "U5") (pin "10") (pinfunction "RSVD_10") (pintype "passive"))
      (node (ref "U5") (pin "11") (pinfunction "AVSS_11") (pintype "passive"))
      (node (ref "U5") (pin "12") (pinfunction "RSVD_12") (pintype "passive"))
      (node (ref "U5") (pin "13") (pinfunction "DVSS_13") (pintype "passive"))
      (node (ref "U5") (pin "2") (pinfunction "RSVD_2") (pintype "passive"))
      (node (ref "U5") (pin "3") (pinfunction "RSVD_3") (pintype "passive"))
      (node (ref "U5") (pin "7") (pinfunction "PSS_7") (pintype "passive"))
    )
    (net (code "48") (name "Net-(*1-VDDCORE)") (class "Default")
      (node (ref "*1") (pin "115") (pinfunction "VDDCORE_115") (pintype "passive"))
      (node (ref "C11") (pin "1") (pinfunction "1_1") (pintype "passive"))
      (node (ref "L2") (pin "2") (pinfunction "2_2") (pintype "passive"))
    )
    (net (code "49") (name "Net-(*1-VSW)") (class "Default")
      (node (ref "*1") (pin "117") (pinfunction "VSW_117") (pintype "passive"))
      (node (ref "L2") (pin "1") (pinfunction "1_1") (pintype "passive"))
    )
    (net (code "50") (name "Net-(*2-ANT)") (class "Default")
      (node (ref "*2") (pin "49") (pinfunction "ANT_49") (pintype "passive"))
      (node (ref "P4") (pin "4") (pinfunction "4_4") (pintype "passive"))
    )
    (net (code "51") (name "Net-(*2-MCLR)") (class "Default")
      (node (ref "*2") (pin "13") (pinfunction "MCLR_13") (pintype "passive"))
      (node (ref "C32") (pin "2") (pinfunction "2_2") (pintype "passive"))
    )
    (net (code "52") (name "Net-(*2-RB0)") (class "Default")
      (node (ref "*2") (pin "15") (pinfunction "RB0_15") (pintype "passive"))
      (node (ref "P8") (pin "7") (pinfunction "7_7") (pintype "passive"))
    )
    (net (code "53") (name "Net-(*2-RB1)") (class "Default")
      (node (ref "*2") (pin "14") (pinfunction "RB1_14") (pintype "passive"))
      (node (ref "P8") (pin "8") (pinfunction "8_8") (pintype "passive"))
    )
    (net (code "54") (name "Net-(*2-RB5)") (class "Default")
      (node (ref "*2") (pin "24") (pinfunction "RB5_24") (pintype "passive"))
      (node (ref "P8") (pin "6") (pinfunction "6_6") (pintype "passive"))
    )
    (net (code "55") (name "Net-(*2-RB10)") (class "Default")
      (node (ref "*2") (pin "23") (pinfunction "RB10_23") (pintype "passive"))
      (node (ref "P8") (pin "5") (pinfunction "5_5") (pintype "passive"))
    )
    (net (code "56") (name "Net-(*2-RB11)") (class "Default")
      (node (ref "*2") (pin "22") (pinfunction "RB11_22") (pintype "passive"))
      (node (ref "P8") (pin "4") (pinfunction "4_4") (pintype "passive"))
    )
    (net (code "57") (name "Net-(*2-RB12)") (class "Default")
      (node (ref "*2") (pin "21") (pinfunction "RB12_21") (pintype "passive"))
      (node (ref "P8") (pin "3") (pinfunction "3_3") (pintype "passive"))
    )
    (net (code "58") (name "Net-(*2-RB13)") (class "Default")
      (node (ref "*2") (pin "20") (pinfunction "RB13_20") (pintype "passive"))
      (node (ref "P8") (pin "2") (pinfunction "2_2") (pintype "passive"))
    )
    (net (code "59") (name "Net-(*2-RB15)") (class "Default")
      (node (ref "*2") (pin "2") (pinfunction "RB15_2") (pintype "passive"))
      (node (ref "P8") (pin "1") (pinfunction "1_1") (pintype "passive"))
    )
    (net (code "60") (name "Net-(*2-RC12)") (class "Default")
      (node (ref "*2") (pin "30") (pinfunction "RC12_30") (pintype "passive"))
      (node (ref "P7") (pin "5") (pinfunction "5_5") (pintype "passive"))
    )
    (net (code "61") (name "Net-(*2-RC13)") (class "Default")
      (node (ref "*2") (pin "33") (pinfunction "RC13_33") (pintype "passive"))
      (node (ref "P7") (pin "4") (pinfunction "4_4") (pintype "passive"))
    )
    (net (code "62") (name "Net-(*2-RC14)") (class "Default")
      (node (ref "*2") (pin "34") (pinfunction "RC14_34") (pintype "passive"))
      (node (ref "P7") (pin "3") (pinfunction "3_3") (pintype "passive"))
    )
    (net (code "63") (name "Net-(*2-RC15)") (class "Default")
      (node (ref "*2") (pin "31") (pinfunction "RC15_31") (pintype "passive"))
      (node (ref "P7") (pin "2") (pinfunction "2_2") (pintype "passive"))
    )
    (net (code "64") (name "Net-(*2-RD0)") (class "Default")
      (node (ref "*2") (pin "38") (pinfunction "RD0_38") (pintype "passive"))
      (node (ref "P7") (pin "1") (pinfunction "1_1") (pintype "passive"))
    )
    (net (code "65") (name "Net-(*2-RD1)") (class "Default")
      (node (ref "*2") (pin "47") (pinfunction "RD1_47") (pintype "passive"))
      (node (ref "P5") (pin "10") (pinfunction "10_10") (pintype "passive"))
    )
    (net (code "66") (name "Net-(*2-RD2)") (class "Default")
      (node (ref "*2") (pin "32") (pinfunction "RD2_32") (pintype "passive"))
      (node (ref "P5") (pin "9") (pinfunction "9_9") (pintype "passive"))
    )
    (net (code "67") (name "Net-(*2-RD3)") (class "Default")
      (node (ref "*2") (pin "29") (pinfunction "RD3_29") (pintype "passive"))
      (node (ref "P5") (pin "8") (pinfunction "8_8") (pintype "passive"))
    )
    (net (code "68") (name "Net-(*2-RD4)") (class "Default")
      (node (ref "*2") (pin "39") (pinfunction "RD4_39") (pintype "passive"))
      (node (ref "P5") (pin "7") (pinfunction "7_7") (pintype "passive"))
    )
    (net (code "69") (name "Net-(*2-RD5)") (class "Default")
      (node (ref "*2") (pin "41") (pinfunction "RD5_41") (pintype "passive"))
      (node (ref "P5") (pin "6") (pinfunction "6_6") (pintype "passive"))
    )
    (net (code "70") (name "Net-(*2-RD6)") (class "Default")
      (node (ref "*2") (pin "42") (pinfunction "RD6_42") (pintype "passive"))
      (node (ref "P5") (pin "5") (pinfunction "5_5") (pintype "passive"))
    )
    (net (code "71") (name "Net-(*2-RD7)") (class "Default")
      (node (ref "*2") (pin "43") (pinfunction "RD7_43") (pintype "passive"))
      (node (ref "P5") (pin "4") (pinfunction "4_4") (pintype "passive"))
    )
    (net (code "72") (name "Net-(*2-RD9)") (class "Default")
      (node (ref "*2") (pin "44") (pinfunction "RD9_44") (pintype "passive"))
      (node (ref "P5") (pin "3") (pinfunction "3_3") (pintype "passive"))
    )
    (net (code "73") (name "Net-(*2-RD10)") (class "Default")
      (node (ref "*2") (pin "46") (pinfunction "RD10_46") (pintype "passive"))
      (node (ref "P5") (pin "2") (pinfunction "2_2") (pintype "passive"))
    )
    (net (code "74") (name "Net-(*2-RD11)") (class "Default")
      (node (ref "*2") (pin "37") (pinfunction "RD11_37") (pintype "passive"))
      (node (ref "P5") (pin "1") (pinfunction "1_1") (pintype "passive"))
    )
    (net (code "75") (name "Net-(*2-RE0)") (class "Default")
      (node (ref "*2") (pin "3") (pinfunction "RE0_3") (pintype "passive"))
      (node (ref "P8") (pin "9") (pinfunction "9_9") (pintype "passive"))
    )
    (net (code "76") (name "Net-(*2-RE1)") (class "Default")
      (node (ref "*2") (pin "4") (pinfunction "RE1_4") (pintype "passive"))
      (node (ref "P8") (pin "10") (pinfunction "10_10") (pintype "passive"))
    )
    (net (code "77") (name "Net-(*2-RE2)") (class "Default")
      (node (ref "*2") (pin "5") (pinfunction "RE2_5") (pintype "passive"))
      (node (ref "P6") (pin "1") (pinfunction "1_1") (pintype "passive"))
    )
    (net (code "78") (name "Net-(*2-RE3)") (class "Default")
      (node (ref "*2") (pin "6") (pinfunction "RE3_6") (pintype "passive"))
      (node (ref "P6") (pin "2") (pinfunction "2_2") (pintype "passive"))
    )
    (net (code "79") (name "Net-(*2-RE4)") (class "Default")
      (node (ref "*2") (pin "7") (pinfunction "RE4_7") (pintype "passive"))
      (node (ref "P6") (pin "3") (pinfunction "3_3") (pintype "passive"))
    )
    (net (code "80") (name "Net-(*2-RE5)") (class "Default")
      (node (ref "*2") (pin "10") (pinfunction "RE5_10") (pintype "passive"))
      (node (ref "P6") (pin "4") (pinfunction "4_4") (pintype "passive"))
    )
    (net (code "81") (name "Net-(*2-RE6)") (class "Default")
      (node (ref "*2") (pin "11") (pinfunction "RE6_11") (pintype "passive"))
      (node (ref "P6") (pin "5") (pinfunction "5_5") (pintype "passive"))
    )
    (net (code "82") (name "Net-(*2-RE7)") (class "Default")
      (node (ref "*2") (pin "12") (pinfunction "RE7_12") (pintype "passive"))
      (node (ref "P6") (pin "6") (pinfunction "6_6") (pintype "passive"))
    )
    (net (code "83") (name "Net-(*2-RF3)") (class "Default")
      (node (ref "*2") (pin "18") (pinfunction "RF3_18") (pintype "passive"))
      (node (ref "P7") (pin "6") (pinfunction "6_6") (pintype "passive"))
    )
    (net (code "84") (name "Net-(*2-RG2)") (class "Default")
      (node (ref "*2") (pin "28") (pinfunction "RG2_28") (pintype "passive"))
      (node (ref "P4") (pin "2") (pinfunction "2_2") (pintype "passive"))
    )
    (net (code "85") (name "Net-(*2-RG3)") (class "Default")
      (node (ref "*2") (pin "27") (pinfunction "RG3_27") (pintype "passive"))
      (node (ref "P4") (pin "3") (pinfunction "3_3") (pintype "passive"))
    )
    (net (code "86") (name "Net-(*2-SPI_CLK)") (class "Default")
      (node (ref "*2") (pin "53") (pinfunction "SPI_CLK_53") (pintype "passive"))
      (node (ref "P6") (pin "8") (pinfunction "8_8") (pintype "passive"))
    )
    (net (code "87") (name "Net-(*2-SPI_CS)") (class "Default")
      (node (ref "*2") (pin "55") (pinfunction "SPI_CS_55") (pintype "passive"))
      (node (ref "P6") (pin "10") (pinfunction "10_10") (pintype "passive"))
    )
    (net (code "88") (name "Net-(*2-SPI_MISO)") (class "Default")
      (node (ref "*2") (pin "52") (pinfunction "SPI_MISO_52") (pintype "passive"))
      (node (ref "P6") (pin "7") (pinfunction "7_7") (pintype "passive"))
    )
    (net (code "89") (name "Net-(*2-SPI_MOSI)") (class "Default")
      (node (ref "*2") (pin "54") (pinfunction "SPI_MOSI_54") (pintype "passive"))
      (node (ref "P6") (pin "9") (pinfunction "9_9") (pintype "passive"))
    )
    (net (code "90") (name "Net-(*2-VBUS)") (class "Default")
      (node (ref "*2") (pin "25") (pinfunction "VBUS_25") (pintype "passive"))
      (node (ref "P4") (pin "1") (pinfunction "1_1") (pintype "passive"))
    )
    (net (code "91") (name "Net-(D1-A)") (class "Default")
      (node (ref "D1") (pin "2") (pinfunction "A_2") (pintype "passive"))
      (node (ref "L3") (pin "1") (pinfunction "1_1") (pintype "passive"))
      (node (ref "U3") (pin "9") (pinfunction "VX_9") (pintype "passive"))
    )
    (net (code "92") (name "Net-(D1-K)") (class "Default")
      (node (ref "C24") (pin "1") (pinfunction "1_1") (pintype "passive"))
      (node (ref "D1") (pin "1") (pinfunction "K_1") (pintype "passive"))
      (node (ref "U3") (pin "6") (pinfunction "CP5_6") (pintype "passive"))
    )
    (net (code "93") (name "Net-(D2-A)") (class "Default")
      (node (ref "D2") (pin "2") (pinfunction "A_2") (pintype "passive"))
      (node (ref "L4") (pin "1") (pinfunction "1_1") (pintype "passive"))
      (node (ref "U5") (pin "8") (pinfunction "VX_8") (pintype "passive"))
    )
    (net (code "94") (name "Net-(D2-K)") (class "Default")
      (node (ref "C31") (pin "1") (pinfunction "1_1") (pintype "passive"))
      (node (ref "D2") (pin "1") (pinfunction "K_1") (pintype "passive"))
      (node (ref "U5") (pin "9") (pinfunction "CP5_9") (pintype "passive"))
    )
    (net (code "95") (name "Net-(L1-Pad1)") (class "Default")
      (node (ref "L1") (pin "1") (pinfunction "1_1") (pintype "passive"))
      (node (ref "P1") (pin "3") (pinfunction "3_3") (pintype "passive"))
    )
    (net (code "96") (name "Net-(U3-AVDD)") (class "Default")
      (node (ref "C18") (pin "1") (pinfunction "1_1") (pintype "passive"))
      (node (ref "U3") (pin "2") (pinfunction "AVDD_2") (pintype "passive"))
    )
    (net (code "97") (name "Net-(U3-DVDD)") (class "Default")
      (node (ref "C19") (pin "1") (pinfunction "1_1") (pintype "passive"))
      (node (ref "U3") (pin "4") (pinfunction "DVDD_4") (pintype "passive"))
    )
    (net (code "98") (name "Net-(U4-V1P8ANA)") (class "Default")
      (node (ref "C25") (pin "1") (pinfunction "1_1") (pintype "passive"))
      (node (ref "C26") (pin "1") (pinfunction "1_1") (pintype "passive"))
      (node (ref "U4") (pin "10") (pinfunction "V1P8ANA_10") (pintype "passive"))
    )
    (net (code "99") (name "Net-(U4-V1P8DIG)") (class "Default")
      (node (ref "C22") (pin "1") (pinfunction "1_1") (pintype "passive"))
      (node (ref "C23") (pin "1") (pinfunction "1_1") (pintype "passive"))
      (node (ref "U4") (pin "8") (pinfunction "V1P8DIG_8") (pintype "passive"))
    )
    (net (code "100") (name "Net-(U4-VDDIO)") (class "Default")
      (node (ref "C20") (pin "1") (pinfunction "1_1") (pintype "passive"))
      (node (ref "C21") (pin "1") (pinfunction "1_1") (pintype "passive"))
      (node (ref "U4") (pin "5") (pinfunction "VDDIO_5") (pintype "passive"))
    )
    (net (code "101") (name "Net-(U5-AVDD)") (class "Default")
      (node (ref "C29") (pin "1") (pinfunction "1_1") (pintype "passive"))
      (node (ref "U5") (pin "14") (pinfunction "AVDD_14") (pintype "passive"))
    )
    (net (code "102") (name "Net-(U5-DVDD)") (class "Default")
      (node (ref "C30") (pin "1") (pinfunction "1_1") (pintype "passive"))
      (node (ref "U5") (pin "1") (pinfunction "DVDD_1") (pintype "passive"))
    )
    (net (code "103") (name "VCC") (class "Default")
      (node (ref "SD1") (pin "4") (pinfunction "VDD_4") (pintype "passive"))
    )
    (net (code "104") (name "unconnected-(*1-PA00-Pad1)") (class "Default")
      (node (ref "*1") (pin "1") (pinfunction "PA00_1") (pintype "passive"))
    )
    (net (code "105") (name "unconnected-(*1-PA02-Pad9)") (class "Default")
      (node (ref "*1") (pin "9") (pinfunction "PA02_9") (pintype "passive"))
    )
    (net (code "106") (name "unconnected-(*1-PA03-Pad10)") (class "Default")
      (node (ref "*1") (pin "10") (pinfunction "PA03_10") (pintype "passive"))
    )
    (net (code "107") (name "unconnected-(*1-PA04-Pad21)") (class "Default")
      (node (ref "*1") (pin "21") (pinfunction "PA04_21") (pintype "passive"))
    )
    (net (code "108") (name "unconnected-(*1-PA05-Pad22)") (class "Default")
      (node (ref "*1") (pin "22") (pinfunction "PA05_22") (pintype "passive"))
    )
    (net (code "109") (name "unconnected-(*1-PA06-Pad23)") (class "Default")
      (node (ref "*1") (pin "23") (pinfunction "PA06_23") (pintype "passive"))
    )
    (net (code "110") (name "unconnected-(*1-PA07-Pad24)") (class "Default")
      (node (ref "*1") (pin "24") (pinfunction "PA07_24") (pintype "passive"))
    )
    (net (code "111") (name "unconnected-(*1-PA12-Pad60)") (class "Default")
      (node (ref "*1") (pin "60") (pinfunction "PA12_60") (pintype "passive"))
    )
    (net (code "112") (name "unconnected-(*1-PA13-Pad61)") (class "Default")
      (node (ref "*1") (pin "61") (pinfunction "PA13_61") (pintype "passive"))
    )
    (net (code "113") (name "unconnected-(*1-PA14-Pad62)") (class "Default")
      (node (ref "*1") (pin "62") (pinfunction "PA14_62") (pintype "passive"))
    )
    (net (code "114") (name "unconnected-(*1-PA15-Pad63)") (class "Default")
      (node (ref "*1") (pin "63") (pinfunction "PA15_63") (pintype "passive"))
    )
    (net (code "115") (name "unconnected-(*1-PA19-Pad69)") (class "Default")
      (node (ref "*1") (pin "69") (pinfunction "PA19_69") (pintype "passive"))
    )
    (net (code "116") (name "unconnected-(*1-PA20-Pad88)") (class "Default")
      (node (ref "*1") (pin "88") (pinfunction "PA20_88") (pintype "passive"))
    )
    (net (code "117") (name "unconnected-(*1-PA21-Pad89)") (class "Default")
      (node (ref "*1") (pin "89") (pinfunction "PA21_89") (pintype "passive"))
    )
    (net (code "118") (name "unconnected-(*1-PA22-Pad92)") (class "Default")
      (node (ref "*1") (pin "92") (pinfunction "PA22_92") (pintype "passive"))
    )
    (net (code "119") (name "unconnected-(*1-PA23-Pad93)") (class "Default")
      (node (ref "*1") (pin "93") (pinfunction "PA23_93") (pintype "passive"))
    )
    (net (code "120") (name "unconnected-(*1-PA24-Pad94)") (class "Default")
      (node (ref "*1") (pin "94") (pinfunction "PA24_94") (pintype "passive"))
    )
    (net (code "121") (name "unconnected-(*1-PA25-Pad95)") (class "Default")
      (node (ref "*1") (pin "95") (pinfunction "PA25_95") (pintype "passive"))
    )
    (net (code "122") (name "unconnected-(*1-PA27-Pad113)") (class "Default")
      (node (ref "*1") (pin "113") (pinfunction "PA27_113") (pintype "passive"))
    )
    (net (code "123") (name "unconnected-(*1-PB00-Pad125)") (class "Default")
      (node (ref "*1") (pin "125") (pinfunction "PB00_125") (pintype "passive"))
    )
    (net (code "124") (name "unconnected-(*1-PB01-Pad126)") (class "Default")
      (node (ref "*1") (pin "126") (pinfunction "PB01_126") (pintype "passive"))
    )
    (net (code "125") (name "unconnected-(*1-PB02-Pad127)") (class "Default")
      (node (ref "*1") (pin "127") (pinfunction "PB02_127") (pintype "passive"))
    )
    (net (code "126") (name "unconnected-(*1-PB03-Pad128)") (class "Default")
      (node (ref "*1") (pin "128") (pinfunction "PB03_128") (pintype "passive"))
    )
    (net (code "127") (name "unconnected-(*1-PB04-Pad11)") (class "Default")
      (node (ref "*1") (pin "11") (pinfunction "PB04_11") (pintype "passive"))
    )
    (net (code "128") (name "unconnected-(*1-PB05-Pad12)") (class "Default")
      (node (ref "*1") (pin "12") (pinfunction "PB05_12") (pintype "passive"))
    )
    (net (code "129") (name "unconnected-(*1-PB06-Pad17)") (class "Default")
      (node (ref "*1") (pin "17") (pinfunction "PB06_17") (pintype "passive"))
    )
    (net (code "130") (name "unconnected-(*1-PB07-Pad18)") (class "Default")
      (node (ref "*1") (pin "18") (pinfunction "PB07_18") (pintype "passive"))
    )
    (net (code "131") (name "unconnected-(*1-PB08-Pad19)") (class "Default")
      (node (ref "*1") (pin "19") (pinfunction "PB08_19") (pintype "passive"))
    )
    (net (code "132") (name "unconnected-(*1-PB09-Pad20)") (class "Default")
      (node (ref "*1") (pin "20") (pinfunction "PB09_20") (pintype "passive"))
    )
    (net (code "133") (name "unconnected-(*1-PB16-Pad82)") (class "Default")
      (node (ref "*1") (pin "82") (pinfunction "PB16_82") (pintype "passive"))
    )
    (net (code "134") (name "unconnected-(*1-PB17-Pad83)") (class "Default")
      (node (ref "*1") (pin "83") (pinfunction "PB17_83") (pintype "passive"))
    )
    (net (code "135") (name "unconnected-(*1-PB18-Pad84)") (class "Default")
      (node (ref "*1") (pin "84") (pinfunction "PB18_84") (pintype "passive"))
    )
    (net (code "136") (name "unconnected-(*1-PB19-Pad85)") (class "Default")
      (node (ref "*1") (pin "85") (pinfunction "PB19_85") (pintype "passive"))
    )
    (net (code "137") (name "unconnected-(*1-PB20-Pad86)") (class "Default")
      (node (ref "*1") (pin "86") (pinfunction "PB20_86") (pintype "passive"))
    )
    (net (code "138") (name "unconnected-(*1-PB21-Pad87)") (class "Default")
      (node (ref "*1") (pin "87") (pinfunction "PB21_87") (pintype "passive"))
    )
    (net (code "139") (name "unconnected-(*1-PB22-Pad98)") (class "Default")
      (node (ref "*1") (pin "98") (pinfunction "PB22_98") (pintype "passive"))
    )
    (net (code "140") (name "unconnected-(*1-PB23-Pad99)") (class "Default")
      (node (ref "*1") (pin "99") (pinfunction "PB23_99") (pintype "passive"))
    )
    (net (code "141") (name "unconnected-(*1-PB24-Pad100)") (class "Default")
      (node (ref "*1") (pin "100") (pinfunction "PB24_100") (pintype "passive"))
    )
    (net (code "142") (name "unconnected-(*1-PB25-Pad101)") (class "Default")
      (node (ref "*1") (pin "101") (pinfunction "PB25_101") (pintype "passive"))
    )
    (net (code "143") (name "unconnected-(*1-PB26-Pad102)") (class "Default")
      (node (ref "*1") (pin "102") (pinfunction "PB26_102") (pintype "passive"))
    )
    (net (code "144") (name "unconnected-(*1-PB27-Pad103)") (class "Default")
      (node (ref "*1") (pin "103") (pinfunction "PB27_103") (pintype "passive"))
    )
    (net (code "145") (name "unconnected-(*1-PB28-Pad104)") (class "Default")
      (node (ref "*1") (pin "104") (pinfunction "PB28_104") (pintype "passive"))
    )
    (net (code "146") (name "unconnected-(*1-PB29-Pad105)") (class "Default")
      (node (ref "*1") (pin "105") (pinfunction "PB29_105") (pintype "passive"))
    )
    (net (code "147") (name "unconnected-(*1-PB30-Pad121)") (class "Default")
      (node (ref "*1") (pin "121") (pinfunction "PB30_121") (pintype "passive"))
    )
    (net (code "148") (name "unconnected-(*1-PB31-Pad122)") (class "Default")
      (node (ref "*1") (pin "122") (pinfunction "PB31_122") (pintype "passive"))
    )
    (net (code "149") (name "unconnected-(*1-PC01-Pad4)") (class "Default")
      (node (ref "*1") (pin "4") (pinfunction "PC01_4") (pintype "passive"))
    )
    (net (code "150") (name "unconnected-(*1-PC02-Pad7)") (class "Default")
      (node (ref "*1") (pin "7") (pinfunction "PC02_7") (pintype "passive"))
    )
    (net (code "151") (name "unconnected-(*1-PC03-Pad8)") (class "Default")
      (node (ref "*1") (pin "8") (pinfunction "PC03_8") (pintype "passive"))
    )
    (net (code "152") (name "unconnected-(*1-PC14-Pad58)") (class "Default")
      (node (ref "*1") (pin "58") (pinfunction "PC14_58") (pintype "passive"))
    )
    (net (code "153") (name "unconnected-(*1-PC15-Pad59)") (class "Default")
      (node (ref "*1") (pin "59") (pinfunction "PC15_59") (pintype "passive"))
    )
    (net (code "154") (name "unconnected-(*1-PC16-Pad70)") (class "Default")
      (node (ref "*1") (pin "70") (pinfunction "PC16_70") (pintype "passive"))
    )
    (net (code "155") (name "unconnected-(*1-PC17-Pad71)") (class "Default")
      (node (ref "*1") (pin "71") (pinfunction "PC17_71") (pintype "passive"))
    )
    (net (code "156") (name "unconnected-(*1-PC18-Pad72)") (class "Default")
      (node (ref "*1") (pin "72") (pinfunction "PC18_72") (pintype "passive"))
    )
    (net (code "157") (name "unconnected-(*1-PC19-Pad73)") (class "Default")
      (node (ref "*1") (pin "73") (pinfunction "PC19_73") (pintype "passive"))
    )
    (net (code "158") (name "unconnected-(*1-PC20-Pad74)") (class "Default")
      (node (ref "*1") (pin "74") (pinfunction "PC20_74") (pintype "passive"))
    )
    (net (code "159") (name "unconnected-(*1-PC21-Pad75)") (class "Default")
      (node (ref "*1") (pin "75") (pinfunction "PC21_75") (pintype "passive"))
    )
    (net (code "160") (name "unconnected-(*1-PC22-Pad76)") (class "Default")
      (node (ref "*1") (pin "76") (pinfunction "PC22_76") (pintype "passive"))
    )
    (net (code "161") (name "unconnected-(*1-PC23-Pad77)") (class "Default")
      (node (ref "*1") (pin "77") (pinfunction "PC23_77") (pintype "passive"))
    )
    (net (code "162") (name "unconnected-(*1-PC24-Pad108)") (class "Default")
      (node (ref "*1") (pin "108") (pinfunction "PC24_108") (pintype "passive"))
    )
    (net (code "163") (name "unconnected-(*1-PC25-Pad109)") (class "Default")
      (node (ref "*1") (pin "109") (pinfunction "PC25_109") (pintype "passive"))
    )
    (net (code "164") (name "unconnected-(*1-PC26-Pad110)") (class "Default")
      (node (ref "*1") (pin "110") (pinfunction "PC26_110") (pintype "passive"))
    )
    (net (code "165") (name "unconnected-(*1-PC27-Pad111)") (class "Default")
      (node (ref "*1") (pin "111") (pinfunction "PC27_111") (pintype "passive"))
    )
    (net (code "166") (name "unconnected-(*1-PC28-Pad112)") (class "Default")
      (node (ref "*1") (pin "112") (pinfunction "PC28_112") (pintype "passive"))
    )
    (net (code "167") (name "unconnected-(*1-PC30-Pad123)") (class "Default")
      (node (ref "*1") (pin "123") (pinfunction "PC30_123") (pintype "passive"))
    )
    (net (code "168") (name "unconnected-(*1-PC31-Pad124)") (class "Default")
      (node (ref "*1") (pin "124") (pinfunction "PC31_124") (pintype "passive"))
    )
    (net (code "169") (name "unconnected-(*1-PD00-Pad13)") (class "Default")
      (node (ref "*1") (pin "13") (pinfunction "PD00_13") (pintype "passive"))
    )
    (net (code "170") (name "unconnected-(*1-PD01-Pad16)") (class "Default")
      (node (ref "*1") (pin "16") (pinfunction "PD01_16") (pintype "passive"))
    )
    (net (code "171") (name "unconnected-(*1-PD20-Pad80)") (class "Default")
      (node (ref "*1") (pin "80") (pinfunction "PD20_80") (pintype "passive"))
    )
    (net (code "172") (name "unconnected-(*1-PD21-Pad81)") (class "Default")
      (node (ref "*1") (pin "81") (pinfunction "PD21_81") (pintype "passive"))
    )
    (net (code "173") (name "unconnected-(P1-PadMP1)") (class "Default")
      (node (ref "P1") (pin "MP1") (pinfunction "MP1_MP1") (pintype "passive"))
    )
    (net (code "174") (name "unconnected-(P1-PadMP2)") (class "Default")
      (node (ref "P1") (pin "MP2") (pinfunction "MP2_MP2") (pintype "passive"))
    )
    (net (code "175") (name "unconnected-(P2-Pad6)") (class "Default")
      (node (ref "P2") (pin "6") (pinfunction "6_6") (pintype "passive"))
    )
    (net (code "176") (name "unconnected-(P2-Pad7)") (class "Default")
      (node (ref "P2") (pin "7") (pinfunction "7_7") (pintype "passive"))
    )
    (net (code "177") (name "unconnected-(P2-Pad8)") (class "Default")
      (node (ref "P2") (pin "8") (pinfunction "8_8") (pintype "passive"))
    )
    (net (code "178") (name "unconnected-(P2-Pad9)") (class "Default")
      (node (ref "P2") (pin "9") (pinfunction "9_9") (pintype "passive"))
    )
    (net (code "179") (name "unconnected-(P3-Pad6)") (class "Default")
      (node (ref "P3") (pin "6") (pinfunction "6_6") (pintype "passive"))
    )
    (net (code "180") (name "unconnected-(P3-Pad7)") (class "Default")
      (node (ref "P3") (pin "7") (pinfunction "7_7") (pintype "passive"))
    )
    (net (code "181") (name "unconnected-(P3-Pad8)") (class "Default")
      (node (ref "P3") (pin "8") (pinfunction "8_8") (pintype "passive"))
    )
    (net (code "182") (name "unconnected-(P3-Pad9)") (class "Default")
      (node (ref "P3") (pin "9") (pinfunction "9_9") (pintype "passive"))
    )
    (net (code "183") (name "unconnected-(P4-PadMP1)") (class "Default")
      (node (ref "P4") (pin "MP1") (pinfunction "MP1_MP1") (pintype "passive"))
    )
    (net (code "184") (name "unconnected-(P4-PadMP2)") (class "Default")
      (node (ref "P4") (pin "MP2") (pinfunction "MP2_MP2") (pintype "passive"))
    )
    (net (code "185") (name "unconnected-(P5-PadMP1)") (class "Default")
      (node (ref "P5") (pin "MP1") (pinfunction "MP1_MP1") (pintype "passive"))
    )
    (net (code "186") (name "unconnected-(P5-PadMP2)") (class "Default")
      (node (ref "P5") (pin "MP2") (pinfunction "MP2_MP2") (pintype "passive"))
    )
    (net (code "187") (name "unconnected-(P6-PadMP1)") (class "Default")
      (node (ref "P6") (pin "MP1") (pinfunction "MP1_MP1") (pintype "passive"))
    )
    (net (code "188") (name "unconnected-(P6-PadMP2)") (class "Default")
      (node (ref "P6") (pin "MP2") (pinfunction "MP2_MP2") (pintype "passive"))
    )
    (net (code "189") (name "unconnected-(P7-PadMP1)") (class "Default")
      (node (ref "P7") (pin "MP1") (pinfunction "MP1_MP1") (pintype "passive"))
    )
    (net (code "190") (name "unconnected-(P7-PadMP2)") (class "Default")
      (node (ref "P7") (pin "MP2") (pinfunction "MP2_MP2") (pintype "passive"))
    )
    (net (code "191") (name "unconnected-(P8-PadMP1)") (class "Default")
      (node (ref "P8") (pin "MP1") (pinfunction "MP1_MP1") (pintype "passive"))
    )
    (net (code "192") (name "unconnected-(P8-PadMP2)") (class "Default")
      (node (ref "P8") (pin "MP2") (pinfunction "MP2_MP2") (pintype "passive"))
    )
    (net (code "193") (name "unconnected-(SD1-CD_A-Pad9)") (class "Default")
      (node (ref "SD1") (pin "9") (pinfunction "CD_A_9") (pintype "passive"))
    )
    (net (code "194") (name "unconnected-(SD1-CD_B-Pad10)") (class "Default")
      (node (ref "SD1") (pin "10") (pinfunction "CD_B_10") (pintype "passive"))
    )
    (net (code "195") (name "unconnected-(U2-GND-Pad18)") (class "Default")
      (node (ref "U2") (pin "18") (pinfunction "GND_18") (pintype "power_in"))
    )
    (net (code "196") (name "unconnected-(U2-GND-Pad35)") (class "Default")
      (node (ref "U2") (pin "35") (pinfunction "GND_35") (pintype "power_in"))
    )
    (net (code "197") (name "unconnected-(U2-GND-Pad42)") (class "Default")
      (node (ref "U2") (pin "42") (pinfunction "GND_42") (pintype "power_in"))
    )
    (net (code "198") (name "unconnected-(U2-GNDANA-Pad5)") (class "Default")
      (node (ref "U2") (pin "5") (pinfunction "GNDANA_5") (pintype "power_in"))
    )
    (net (code "199") (name "unconnected-(U2-PA00-Pad1)") (class "Default")
      (node (ref "U2") (pin "1") (pinfunction "PA00_1") (pintype "bidirectional"))
    )
    (net (code "200") (name "unconnected-(U2-PA01-Pad2)") (class "Default")
      (node (ref "U2") (pin "2") (pinfunction "PA01_2") (pintype "bidirectional"))
    )
    (net (code "201") (name "unconnected-(U2-PA02-Pad3)") (class "Default")
      (node (ref "U2") (pin "3") (pinfunction "PA02_3") (pintype "bidirectional"))
    )
    (net (code "202") (name "unconnected-(U2-PA03-Pad4)") (class "Default")
      (node (ref "U2") (pin "4") (pinfunction "PA03_4") (pintype "bidirectional"))
    )
    (net (code "203") (name "unconnected-(U2-PA04-Pad9)") (class "Default")
      (node (ref "U2") (pin "9") (pinfunction "PA04_9") (pintype "bidirectional"))
    )
    (net (code "204") (name "unconnected-(U2-PA05-Pad10)") (class "Default")
      (node (ref "U2") (pin "10") (pinfunction "PA05_10") (pintype "bidirectional"))
    )
    (net (code "205") (name "unconnected-(U2-PA06-Pad11)") (class "Default")
      (node (ref "U2") (pin "11") (pinfunction "PA06_11") (pintype "bidirectional"))
    )
    (net (code "206") (name "unconnected-(U2-PA07-Pad12)") (class "Default")
      (node (ref "U2") (pin "12") (pinfunction "PA07_12") (pintype "bidirectional"))
    )
    (net (code "207") (name "unconnected-(U2-PA12-Pad21)") (class "Default")
      (node (ref "U2") (pin "21") (pinfunction "PA12_21") (pintype "bidirectional"))
    )
    (net (code "208") (name "unconnected-(U2-PA13-Pad22)") (class "Default")
      (node (ref "U2") (pin "22") (pinfunction "PA13_22") (pintype "bidirectional"))
    )
    (net (code "209") (name "unconnected-(U2-PA14-Pad23)") (class "Default")
      (node (ref "U2") (pin "23") (pinfunction "PA14_23") (pintype "bidirectional"))
    )
    (net (code "210") (name "unconnected-(U2-PA15-Pad24)") (class "Default")
      (node (ref "U2") (pin "24") (pinfunction "PA15_24") (pintype "bidirectional"))
    )
    (net (code "211") (name "unconnected-(U2-PA16-Pad25)") (class "Default")
      (node (ref "U2") (pin "25") (pinfunction "PA16_25") (pintype "bidirectional"))
    )
    (net (code "212") (name "unconnected-(U2-PA17-Pad26)") (class "Default")
      (node (ref "U2") (pin "26") (pinfunction "PA17_26") (pintype "bidirectional"))
    )
    (net (code "213") (name "unconnected-(U2-PA18-Pad27)") (class "Default")
      (node (ref "U2") (pin "27") (pinfunction "PA18_27") (pintype "bidirectional"))
    )
    (net (code "214") (name "unconnected-(U2-PA19-Pad28)") (class "Default")
      (node (ref "U2") (pin "28") (pinfunction "PA19_28") (pintype "bidirectional"))
    )
    (net (code "215") (name "unconnected-(U2-PA20-Pad29)") (class "Default")
      (node (ref "U2") (pin "29") (pinfunction "PA20_29") (pintype "bidirectional"))
    )
    (net (code "216") (name "unconnected-(U2-PA21-Pad30)") (class "Default")
      (node (ref "U2") (pin "30") (pinfunction "PA21_30") (pintype "bidirectional"))
    )
    (net (code "217") (name "unconnected-(U2-PA22-Pad31)") (class "Default")
      (node (ref "U2") (pin "31") (pinfunction "PA22_31") (pintype "bidirectional"))
    )
    (net (code "218") (name "unconnected-(U2-PA23-Pad32)") (class "Default")
      (node (ref "U2") (pin "32") (pinfunction "PA23_32") (pintype "bidirectional"))
    )
    (net (code "219") (name "unconnected-(U2-PA24-Pad33)") (class "Default")
      (node (ref "U2") (pin "33") (pinfunction "PA24_33") (pintype "bidirectional"))
    )
    (net (code "220") (name "unconnected-(U2-PA25-Pad34)") (class "Default")
      (node (ref "U2") (pin "34") (pinfunction "PA25_34") (pintype "bidirectional"))
    )
    (net (code "221") (name "unconnected-(U2-PA27-Pad39)") (class "Default")
      (node (ref "U2") (pin "39") (pinfunction "PA27_39") (pintype "bidirectional"))
    )
    (net (code "222") (name "unconnected-(U2-PA28-Pad41)") (class "Default")
      (node (ref "U2") (pin "41") (pinfunction "PA28_41") (pintype "bidirectional"))
    )
    (net (code "223") (name "unconnected-(U2-PB02-Pad47)") (class "Default")
      (node (ref "U2") (pin "47") (pinfunction "PB02_47") (pintype "bidirectional"))
    )
    (net (code "224") (name "unconnected-(U2-PB03-Pad48)") (class "Default")
      (node (ref "U2") (pin "48") (pinfunction "PB03_48") (pintype "bidirectional"))
    )
    (net (code "225") (name "unconnected-(U2-PB08-Pad7)") (class "Default")
      (node (ref "U2") (pin "7") (pinfunction "PB08_7") (pintype "bidirectional"))
    )
    (net (code "226") (name "unconnected-(U2-PB09-Pad8)") (class "Default")
      (node (ref "U2") (pin "8") (pinfunction "PB09_8") (pintype "bidirectional"))
    )
    (net (code "227") (name "unconnected-(U2-VDDANA-Pad6)") (class "Default")
      (node (ref "U2") (pin "6") (pinfunction "VDDANA_6") (pintype "power_in"))
    )
    (net (code "228") (name "unconnected-(U2-VDDCORE-Pad43)") (class "Default")
      (node (ref "U2") (pin "43") (pinfunction "VDDCORE_43") (pintype "power_in"))
    )
    (net (code "229") (name "unconnected-(U2-VDDIN-Pad44)") (class "Default")
      (node (ref "U2") (pin "44") (pinfunction "VDDIN_44") (pintype "power_in"))
    )
    (net (code "230") (name "unconnected-(U2-VDDIO-Pad17)") (class "Default")
      (node (ref "U2") (pin "17") (pinfunction "VDDIO_17") (pintype "power_in"))
    )
    (net (code "231") (name "unconnected-(U2-VDDIO-Pad36)") (class "Default")
      (node (ref "U2") (pin "36") (pinfunction "VDDIO_36") (pintype "power_in"))
    )
  )
)
